# LAN8870_PINOUT.net
KiCad netlist of a schematic drawn in Altium Designer
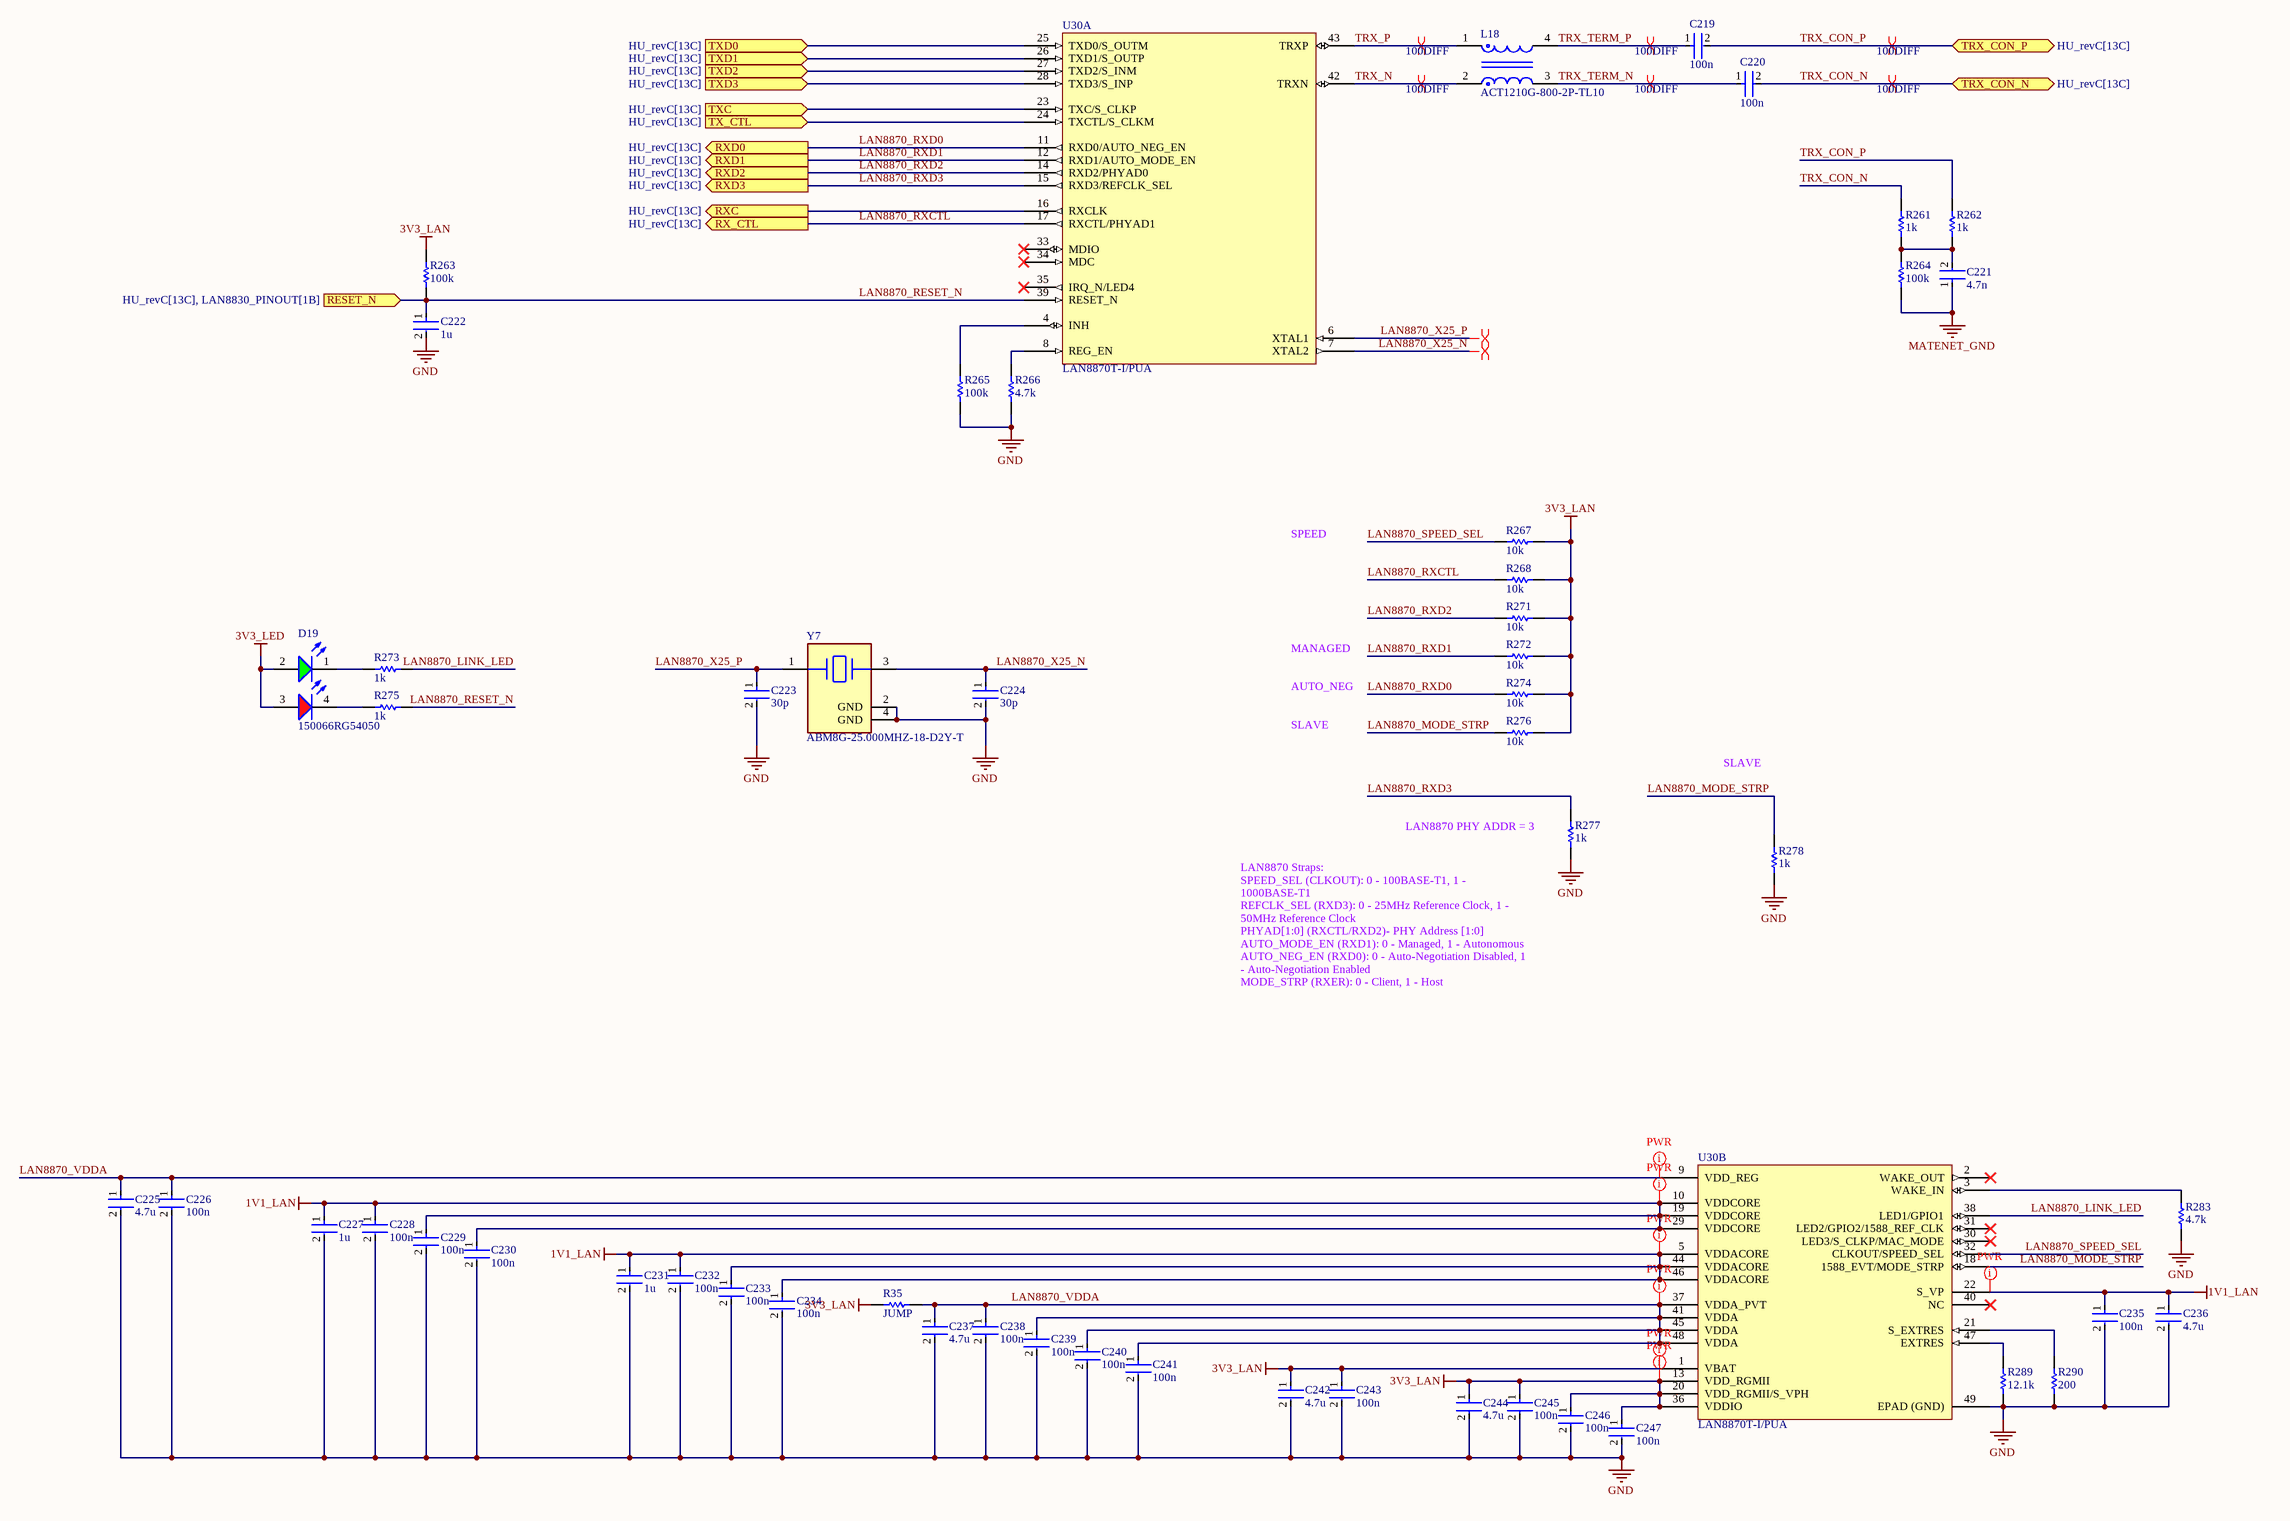
[diagram p0: LAN8870_PINOUT.SchDoc]

(export (version "E")
  (design (tool "Eeschema 10.0.6"))
  (components
    (comp (ref "C219")
      (value "100n")
      (footprint "FP-0402-L_1_0_0_05-W_0_5-IPC_A")
      (description "LARGE PADS, 0402 CAP, CHANGE COMMENT TO MATCH REAL P/N")
      (libsource (lib "Space Concordia") (part "b4654b650e69147ec39a6b967a45e02"))
    )
    (comp (ref "C220")
      (value "100n")
      (footprint "FP-0402-L_1_0_0_05-W_0_5-IPC_A")
      (description "LARGE PADS, 0402 CAP, CHANGE COMMENT TO MATCH REAL P/N")
      (libsource (lib "Space Concordia") (part "b4654b650e69147ec39a6b967a45e02"))
    )
    (comp (ref "C221")
      (value "4.7n")
      (footprint "FP-0402-L_1_0_0_05-W_0_5-IPC_A")
      (description "LARGE PADS, 0402 CAP, CHANGE COMMENT TO MATCH REAL P/N")
      (libsource (lib "Space Concordia") (part "b4654b650e69147ec39a6b967a45e02"))
    )
    (comp (ref "C222")
      (value "1u")
      (footprint "FP-0402-L_1_0_0_05-W_0_5-IPC_A")
      (description "LARGE PADS, 0402 CAP, CHANGE COMMENT TO MATCH REAL P/N")
      (libsource (lib "Space Concordia") (part "b4654b650e69147ec39a6b967a45e02"))
    )
    (comp (ref "C223")
      (value "30p")
      (footprint "FP-0402-L_1_0_0_05-W_0_5-IPC_A")
      (description "LARGE PADS, 0402 CAP, CHANGE COMMENT TO MATCH REAL P/N")
      (libsource (lib "Space Concordia") (part "b4654b650e69147ec39a6b967a45e02"))
    )
    (comp (ref "C224")
      (value "30p")
      (footprint "FP-0402-L_1_0_0_05-W_0_5-IPC_A")
      (description "LARGE PADS, 0402 CAP, CHANGE COMMENT TO MATCH REAL P/N")
      (libsource (lib "Space Concordia") (part "b4654b650e69147ec39a6b967a45e02"))
    )
    (comp (ref "C225")
      (value "4.7u")
      (footprint "FP-0402-L_1_0_0_05-W_0_5-IPC_A")
      (description "LARGE PADS, 0402 CAP, CHANGE COMMENT TO MATCH REAL P/N")
      (libsource (lib "Space Concordia") (part "b4654b650e69147ec39a6b967a45e02"))
    )
    (comp (ref "C226")
      (value "100n")
      (footprint "FP-0402-L_1_0_0_05-W_0_5-IPC_A")
      (description "LARGE PADS, 0402 CAP, CHANGE COMMENT TO MATCH REAL P/N")
      (libsource (lib "Space Concordia") (part "b4654b650e69147ec39a6b967a45e02"))
    )
    (comp (ref "C227")
      (value "1u")
      (footprint "FP-0402-L_1_0_0_05-W_0_5-IPC_A")
      (description "LARGE PADS, 0402 CAP, CHANGE COMMENT TO MATCH REAL P/N")
      (libsource (lib "Space Concordia") (part "b4654b650e69147ec39a6b967a45e02"))
    )
    (comp (ref "C228")
      (value "100n")
      (footprint "FP-0402-L_1_0_0_05-W_0_5-IPC_A")
      (description "LARGE PADS, 0402 CAP, CHANGE COMMENT TO MATCH REAL P/N")
      (libsource (lib "Space Concordia") (part "b4654b650e69147ec39a6b967a45e02"))
    )
    (comp (ref "C229")
      (value "100n")
      (footprint "FP-0402-L_1_0_0_05-W_0_5-IPC_A")
      (description "LARGE PADS, 0402 CAP, CHANGE COMMENT TO MATCH REAL P/N")
      (libsource (lib "Space Concordia") (part "b4654b650e69147ec39a6b967a45e02"))
    )
    (comp (ref "C230")
      (value "100n")
      (footprint "FP-0402-L_1_0_0_05-W_0_5-IPC_A")
      (description "LARGE PADS, 0402 CAP, CHANGE COMMENT TO MATCH REAL P/N")
      (libsource (lib "Space Concordia") (part "b4654b650e69147ec39a6b967a45e02"))
    )
    (comp (ref "C231")
      (value "1u")
      (footprint "FP-0402-L_1_0_0_05-W_0_5-IPC_A")
      (description "LARGE PADS, 0402 CAP, CHANGE COMMENT TO MATCH REAL P/N")
      (libsource (lib "Space Concordia") (part "b4654b650e69147ec39a6b967a45e02"))
    )
    (comp (ref "C232")
      (value "100n")
      (footprint "FP-0402-L_1_0_0_05-W_0_5-IPC_A")
      (description "LARGE PADS, 0402 CAP, CHANGE COMMENT TO MATCH REAL P/N")
      (libsource (lib "Space Concordia") (part "b4654b650e69147ec39a6b967a45e02"))
    )
    (comp (ref "C233")
      (value "100n")
      (footprint "FP-0402-L_1_0_0_05-W_0_5-IPC_A")
      (description "LARGE PADS, 0402 CAP, CHANGE COMMENT TO MATCH REAL P/N")
      (libsource (lib "Space Concordia") (part "b4654b650e69147ec39a6b967a45e02"))
    )
    (comp (ref "C234")
      (value "100n")
      (footprint "FP-0402-L_1_0_0_05-W_0_5-IPC_A")
      (description "LARGE PADS, 0402 CAP, CHANGE COMMENT TO MATCH REAL P/N")
      (libsource (lib "Space Concordia") (part "b4654b650e69147ec39a6b967a45e02"))
    )
    (comp (ref "C235")
      (value "100n")
      (footprint "FP-0402-L_1_0_0_05-W_0_5-IPC_A")
      (description "LARGE PADS, 0402 CAP, CHANGE COMMENT TO MATCH REAL P/N")
      (libsource (lib "Space Concordia") (part "b4654b650e69147ec39a6b967a45e02"))
    )
    (comp (ref "C236")
      (value "4.7u")
      (footprint "FP-0402-L_1_0_0_05-W_0_5-IPC_A")
      (description "LARGE PADS, 0402 CAP, CHANGE COMMENT TO MATCH REAL P/N")
      (libsource (lib "Space Concordia") (part "b4654b650e69147ec39a6b967a45e02"))
    )
    (comp (ref "C237")
      (value "4.7u")
      (footprint "FP-0402-L_1_0_0_05-W_0_5-IPC_A")
      (description "LARGE PADS, 0402 CAP, CHANGE COMMENT TO MATCH REAL P/N")
      (libsource (lib "Space Concordia") (part "b4654b650e69147ec39a6b967a45e02"))
    )
    (comp (ref "C238")
      (value "100n")
      (footprint "FP-0402-L_1_0_0_05-W_0_5-IPC_A")
      (description "LARGE PADS, 0402 CAP, CHANGE COMMENT TO MATCH REAL P/N")
      (libsource (lib "Space Concordia") (part "b4654b650e69147ec39a6b967a45e02"))
    )
    (comp (ref "C239")
      (value "100n")
      (footprint "FP-0402-L_1_0_0_05-W_0_5-IPC_A")
      (description "LARGE PADS, 0402 CAP, CHANGE COMMENT TO MATCH REAL P/N")
      (libsource (lib "Space Concordia") (part "b4654b650e69147ec39a6b967a45e02"))
    )
    (comp (ref "C240")
      (value "100n")
      (footprint "FP-0402-L_1_0_0_05-W_0_5-IPC_A")
      (description "LARGE PADS, 0402 CAP, CHANGE COMMENT TO MATCH REAL P/N")
      (libsource (lib "Space Concordia") (part "b4654b650e69147ec39a6b967a45e02"))
    )
    (comp (ref "C241")
      (value "100n")
      (footprint "FP-0402-L_1_0_0_05-W_0_5-IPC_A")
      (description "LARGE PADS, 0402 CAP, CHANGE COMMENT TO MATCH REAL P/N")
      (libsource (lib "Space Concordia") (part "b4654b650e69147ec39a6b967a45e02"))
    )
    (comp (ref "C242")
      (value "4.7u")
      (footprint "FP-0402-L_1_0_0_05-W_0_5-IPC_A")
      (description "LARGE PADS, 0402 CAP, CHANGE COMMENT TO MATCH REAL P/N")
      (libsource (lib "Space Concordia") (part "b4654b650e69147ec39a6b967a45e02"))
    )
    (comp (ref "C243")
      (value "100n")
      (footprint "FP-0402-L_1_0_0_05-W_0_5-IPC_A")
      (description "LARGE PADS, 0402 CAP, CHANGE COMMENT TO MATCH REAL P/N")
      (libsource (lib "Space Concordia") (part "b4654b650e69147ec39a6b967a45e02"))
    )
    (comp (ref "C244")
      (value "4.7u")
      (footprint "FP-0402-L_1_0_0_05-W_0_5-IPC_A")
      (description "LARGE PADS, 0402 CAP, CHANGE COMMENT TO MATCH REAL P/N")
      (libsource (lib "Space Concordia") (part "b4654b650e69147ec39a6b967a45e02"))
    )
    (comp (ref "C245")
      (value "100n")
      (footprint "FP-0402-L_1_0_0_05-W_0_5-IPC_A")
      (description "LARGE PADS, 0402 CAP, CHANGE COMMENT TO MATCH REAL P/N")
      (libsource (lib "Space Concordia") (part "b4654b650e69147ec39a6b967a45e02"))
    )
    (comp (ref "C246")
      (value "100n")
      (footprint "FP-0402-L_1_0_0_05-W_0_5-IPC_A")
      (description "LARGE PADS, 0402 CAP, CHANGE COMMENT TO MATCH REAL P/N")
      (libsource (lib "Space Concordia") (part "b4654b650e69147ec39a6b967a45e02"))
    )
    (comp (ref "C247")
      (value "100n")
      (footprint "FP-0402-L_1_0_0_05-W_0_5-IPC_A")
      (description "LARGE PADS, 0402 CAP, CHANGE COMMENT TO MATCH REAL P/N")
      (libsource (lib "Space Concordia") (part "b4654b650e69147ec39a6b967a45e02"))
    )
    (comp (ref "D19")
      (value "150066RG54050")
      (footprint "WL-SBCD_0606")
      (description "Led, Red/Grn, 180Mcd/230Mcd, 624Nm/525Nm Rohs Compliant: Yes")
      (fields (field (name "SOURCE") "rgled.SchLib"))
      (libsource (lib "Space Concordia") (part "CMP-004-00034-2"))
    )
    (comp (ref "L18")
      (value "ACT1210G-800-2P-TL10")
      (footprint "FP-ACT1210G-800-2P-TL10-MFG")
      (description "CMC 80UH 70MA 2LN 3.8KOHM SMD")
      (libsource (lib "Altium Content Vault") (part "b4b74a627ea9af473eaab86227aab92"))
    )
    (comp (ref "R35")
      (value "JUMP")
      (footprint "R0603B")
      (description "Resistor")
      (libsource (lib "Space Concordia") (part "Resistor"))
    )
    (comp (ref "R261")
      (value "1k")
      (footprint "R0603B")
      (description "Resistor")
      (libsource (lib "Space Concordia") (part "Resistor"))
    )
    (comp (ref "R262")
      (value "1k")
      (footprint "R0603B")
      (description "Resistor")
      (libsource (lib "Space Concordia") (part "Resistor"))
    )
    (comp (ref "R263")
      (value "100k")
      (footprint "R0603B")
      (description "Resistor")
      (libsource (lib "Space Concordia") (part "Resistor"))
    )
    (comp (ref "R264")
      (value "100k")
      (footprint "R0603B")
      (description "Resistor")
      (libsource (lib "Space Concordia") (part "Resistor"))
    )
    (comp (ref "R265")
      (value "100k")
      (footprint "R0603B")
      (description "Resistor")
      (libsource (lib "Space Concordia") (part "Resistor"))
    )
    (comp (ref "R266")
      (value "4.7k")
      (footprint "R0603B")
      (description "Resistor")
      (libsource (lib "Space Concordia") (part "Resistor"))
    )
    (comp (ref "R267")
      (value "10k")
      (footprint "R0603B")
      (description "Resistor")
      (libsource (lib "Space Concordia") (part "Resistor"))
    )
    (comp (ref "R268")
      (value "10k")
      (footprint "R0603B")
      (description "Resistor")
      (libsource (lib "Space Concordia") (part "Resistor"))
    )
    (comp (ref "R271")
      (value "10k")
      (footprint "R0603B")
      (description "Resistor")
      (libsource (lib "Space Concordia") (part "Resistor"))
    )
    (comp (ref "R272")
      (value "10k")
      (footprint "R0603B")
      (description "Resistor")
      (libsource (lib "Space Concordia") (part "Resistor"))
    )
    (comp (ref "R273")
      (value "1k")
      (footprint "R0603B")
      (description "Resistor")
      (libsource (lib "Space Concordia") (part "Resistor"))
    )
    (comp (ref "R274")
      (value "10k")
      (footprint "R0603B")
      (description "Resistor")
      (libsource (lib "Space Concordia") (part "Resistor"))
    )
    (comp (ref "R275")
      (value "1k")
      (footprint "R0603B")
      (description "Resistor")
      (libsource (lib "Space Concordia") (part "Resistor"))
    )
    (comp (ref "R276")
      (value "10k")
      (footprint "R0603B")
      (description "Resistor")
      (libsource (lib "Space Concordia") (part "Resistor"))
    )
    (comp (ref "R277")
      (value "1k")
      (footprint "R0603B")
      (description "Resistor")
      (libsource (lib "Space Concordia") (part "Resistor"))
    )
    (comp (ref "R278")
      (value "1k")
      (footprint "R0603B")
      (description "Resistor")
      (libsource (lib "Space Concordia") (part "Resistor"))
    )
    (comp (ref "R283")
      (value "4.7k")
      (footprint "R0603B")
      (description "Resistor")
      (libsource (lib "Space Concordia") (part "Resistor"))
    )
    (comp (ref "R289")
      (value "12.1k")
      (footprint "R0603B")
      (description "Resistor")
      (libsource (lib "Space Concordia") (part "Resistor"))
    )
    (comp (ref "R290")
      (value "200")
      (footprint "R0603B")
      (description "Resistor")
      (libsource (lib "Space Concordia") (part "Resistor"))
    )
    (comp (ref "U30")
      (value "LAN8870T-I/PUA")
      (footprint "QFN50P700X700X100_HS-49N")
      (description "100/1000BASE-T1 Rgmii/sgmii Phy")
      (libsource (lib "Space Concordia") (part "LAN8870T-I_PUA"))
    )
    (comp (ref "Y7")
      (value "ABM8G-25.000MHZ-18-D2Y-T")
      (footprint "FP-ABM8G-MFG")
      (description "Crystal 25MHz ±20ppm (Tol) ±30ppm (Stability) 18pF FUND 60Ω 4-Pin SMD T/R")
      (fields (field (name "TOLERANCE") "20ppm"))
      (libsource (lib "Altium Content Vault") (part "48e526d86b7f2615d98721063c72f49"))
    )
  )
  (nets
    (net (code "1") (name "/LAN8870_LINK_LED") (class "Default")
      (node (ref "R273") (pin "2") (pinfunction "2_2") (pintype "passive"))
      (node (ref "U30") (pin "38") (pinfunction "LED1/GPIO1_38") (pintype "bidirectional"))
    )
    (net (code "2") (name "/LAN8870_MODE_STRP") (class "Default")
      (node (ref "R276") (pin "1") (pinfunction "1_1") (pintype "passive"))
      (node (ref "R278") (pin "2") (pinfunction "2_2") (pintype "passive"))
      (node (ref "U30") (pin "18") (pinfunction "1588_EVT/MODE_STRP_18") (pintype "bidirectional"))
    )
    (net (code "3") (name "/LAN8870_RESET_N") (class "Default")
      (node (ref "C222") (pin "1") (pinfunction "1_1") (pintype "passive"))
      (node (ref "R263") (pin "2") (pinfunction "2_2") (pintype "passive"))
      (node (ref "R275") (pin "2") (pinfunction "2_2") (pintype "passive"))
      (node (ref "U30") (pin "39") (pinfunction "RESET_N_39") (pintype "input"))
    )
    (net (code "4") (name "/LAN8870_RXCTL") (class "Default")
      (node (ref "R268") (pin "2") (pinfunction "2_2") (pintype "passive"))
      (node (ref "U30") (pin "17") (pinfunction "RXCTL/PHYAD1_17") (pintype "output"))
    )
    (net (code "5") (name "/LAN8870_RXD0") (class "Default")
      (node (ref "R274") (pin "1") (pinfunction "1_1") (pintype "passive"))
      (node (ref "U30") (pin "11") (pinfunction "RXD0/AUTO_NEG_EN_11") (pintype "output"))
    )
    (net (code "6") (name "/LAN8870_RXD1") (class "Default")
      (node (ref "R272") (pin "1") (pinfunction "1_1") (pintype "passive"))
      (node (ref "U30") (pin "12") (pinfunction "RXD1/AUTO_MODE_EN_12") (pintype "output"))
    )
    (net (code "7") (name "/LAN8870_RXD2") (class "Default")
      (node (ref "R271") (pin "1") (pinfunction "1_1") (pintype "passive"))
      (node (ref "U30") (pin "14") (pinfunction "RXD2/PHYAD0_14") (pintype "output"))
    )
    (net (code "8") (name "/LAN8870_RXD3") (class "Default")
      (node (ref "R277") (pin "2") (pinfunction "2_2") (pintype "passive"))
      (node (ref "U30") (pin "15") (pinfunction "RXD3/REFCLK_SEL_15") (pintype "output"))
    )
    (net (code "9") (name "/LAN8870_SPEED_SEL") (class "Default")
      (node (ref "R267") (pin "1") (pinfunction "1_1") (pintype "passive"))
      (node (ref "U30") (pin "32") (pinfunction "CLKOUT/SPEED_SEL_32") (pintype "bidirectional"))
    )
    (net (code "10") (name "/LAN8870_VDDA") (class "Default")
      (node (ref "C225") (pin "1") (pinfunction "1_1") (pintype "passive"))
      (node (ref "C226") (pin "1") (pinfunction "1_1") (pintype "passive"))
      (node (ref "C237") (pin "1") (pinfunction "1_1") (pintype "passive"))
      (node (ref "C238") (pin "1") (pinfunction "1_1") (pintype "passive"))
      (node (ref "C239") (pin "1") (pinfunction "1_1") (pintype "passive"))
      (node (ref "C240") (pin "1") (pinfunction "1_1") (pintype "passive"))
      (node (ref "C241") (pin "1") (pinfunction "1_1") (pintype "passive"))
      (node (ref "R35") (pin "2") (pinfunction "2_2") (pintype "passive"))
      (node (ref "U30") (pin "37") (pinfunction "VDDA_PVT_37") (pintype "power_in"))
      (node (ref "U30") (pin "41") (pinfunction "VDDA_41") (pintype "power_in"))
      (node (ref "U30") (pin "45") (pinfunction "VDDA_45") (pintype "power_in"))
      (node (ref "U30") (pin "48") (pinfunction "VDDA_48") (pintype "power_in"))
      (node (ref "U30") (pin "9") (pinfunction "VDD_REG_9") (pintype "power_in"))
    )
    (net (code "11") (name "/LAN8870_X25_N") (class "Default")
      (node (ref "C224") (pin "1") (pinfunction "1_1") (pintype "passive"))
      (node (ref "U30") (pin "7") (pinfunction "XTAL2_7") (pintype "output"))
      (node (ref "Y7") (pin "3") (pinfunction "3_3") (pintype "passive"))
    )
    (net (code "12") (name "/LAN8870_X25_P") (class "Default")
      (node (ref "C223") (pin "1") (pinfunction "1_1") (pintype "passive"))
      (node (ref "U30") (pin "6") (pinfunction "XTAL1_6") (pintype "input"))
      (node (ref "Y7") (pin "1") (pinfunction "1_1") (pintype "passive"))
    )
    (net (code "13") (name "/RXC") (class "Default")
      (node (ref "U30") (pin "16") (pinfunction "RXCLK_16") (pintype "output"))
    )
    (net (code "14") (name "/TRX_CON_N") (class "Default")
      (node (ref "C220") (pin "2") (pinfunction "2_2") (pintype "passive"))
      (node (ref "R261") (pin "2") (pinfunction "2_2") (pintype "passive"))
    )
    (net (code "15") (name "/TRX_CON_P") (class "Default")
      (node (ref "C219") (pin "2") (pinfunction "2_2") (pintype "passive"))
      (node (ref "R262") (pin "2") (pinfunction "2_2") (pintype "passive"))
    )
    (net (code "16") (name "/TRX_N") (class "Default")
      (node (ref "L18") (pin "2") (pinfunction "2_2") (pintype "passive"))
      (node (ref "U30") (pin "42") (pinfunction "TRXN_42") (pintype "bidirectional"))
    )
    (net (code "17") (name "/TRX_P") (class "Default")
      (node (ref "L18") (pin "1") (pinfunction "1_1") (pintype "passive"))
      (node (ref "U30") (pin "43") (pinfunction "TRXP_43") (pintype "bidirectional"))
    )
    (net (code "18") (name "/TRX_TERM_N") (class "Default")
      (node (ref "C220") (pin "1") (pinfunction "1_1") (pintype "passive"))
      (node (ref "L18") (pin "3") (pinfunction "3_3") (pintype "passive"))
    )
    (net (code "19") (name "/TRX_TERM_P") (class "Default")
      (node (ref "C219") (pin "1") (pinfunction "1_1") (pintype "passive"))
      (node (ref "L18") (pin "4") (pinfunction "4_4") (pintype "passive"))
    )
    (net (code "20") (name "/TXC") (class "Default")
      (node (ref "U30") (pin "23") (pinfunction "TXC/S_CLKP_23") (pintype "input"))
    )
    (net (code "21") (name "/TXD0") (class "Default")
      (node (ref "U30") (pin "25") (pinfunction "TXD0/S_OUTM_25") (pintype "input"))
    )
    (net (code "22") (name "/TXD1") (class "Default")
      (node (ref "U30") (pin "26") (pinfunction "TXD1/S_OUTP_26") (pintype "input"))
    )
    (net (code "23") (name "/TXD2") (class "Default")
      (node (ref "U30") (pin "27") (pinfunction "TXD2/S_INM_27") (pintype "input"))
    )
    (net (code "24") (name "/TXD3") (class "Default")
      (node (ref "U30") (pin "28") (pinfunction "TXD3/S_INP_28") (pintype "input"))
    )
    (net (code "25") (name "/TX_CTL") (class "Default")
      (node (ref "U30") (pin "24") (pinfunction "TXCTL/S_CLKM_24") (pintype "input"))
    )
    (net (code "26") (name "1V1_LAN") (class "Default")
      (node (ref "C227") (pin "1") (pinfunction "1_1") (pintype "passive"))
      (node (ref "C228") (pin "1") (pinfunction "1_1") (pintype "passive"))
      (node (ref "C229") (pin "1") (pinfunction "1_1") (pintype "passive"))
      (node (ref "C230") (pin "1") (pinfunction "1_1") (pintype "passive"))
      (node (ref "C231") (pin "1") (pinfunction "1_1") (pintype "passive"))
      (node (ref "C232") (pin "1") (pinfunction "1_1") (pintype "passive"))
      (node (ref "C233") (pin "1") (pinfunction "1_1") (pintype "passive"))
      (node (ref "C234") (pin "1") (pinfunction "1_1") (pintype "passive"))
      (node (ref "C235") (pin "1") (pinfunction "1_1") (pintype "passive"))
      (node (ref "C236") (pin "1") (pinfunction "1_1") (pintype "passive"))
      (node (ref "U30") (pin "10") (pinfunction "VDDCORE_10") (pintype "power_in"))
      (node (ref "U30") (pin "19") (pinfunction "VDDCORE_19") (pintype "power_in"))
      (node (ref "U30") (pin "22") (pinfunction "S_VP_22") (pintype "passive"))
      (node (ref "U30") (pin "29") (pinfunction "VDDCORE_29") (pintype "power_in"))
      (node (ref "U30") (pin "44") (pinfunction "VDDACORE_44") (pintype "power_in"))
      (node (ref "U30") (pin "46") (pinfunction "VDDACORE_46") (pintype "power_in"))
      (node (ref "U30") (pin "5") (pinfunction "VDDACORE_5") (pintype "power_in"))
    )
    (net (code "27") (name "3V3_LAN") (class "Default")
      (node (ref "C242") (pin "1") (pinfunction "1_1") (pintype "passive"))
      (node (ref "C243") (pin "1") (pinfunction "1_1") (pintype "passive"))
      (node (ref "C244") (pin "1") (pinfunction "1_1") (pintype "passive"))
      (node (ref "C245") (pin "1") (pinfunction "1_1") (pintype "passive"))
      (node (ref "C246") (pin "1") (pinfunction "1_1") (pintype "passive"))
      (node (ref "C247") (pin "1") (pinfunction "1_1") (pintype "passive"))
      (node (ref "R263") (pin "1") (pinfunction "1_1") (pintype "passive"))
      (node (ref "R267") (pin "2") (pinfunction "2_2") (pintype "passive"))
      (node (ref "R268") (pin "1") (pinfunction "1_1") (pintype "passive"))
      (node (ref "R271") (pin "2") (pinfunction "2_2") (pintype "passive"))
      (node (ref "R272") (pin "2") (pinfunction "2_2") (pintype "passive"))
      (node (ref "R274") (pin "2") (pinfunction "2_2") (pintype "passive"))
      (node (ref "R276") (pin "2") (pinfunction "2_2") (pintype "passive"))
      (node (ref "R35") (pin "1") (pinfunction "1_1") (pintype "passive"))
      (node (ref "U30") (pin "1") (pinfunction "VBAT_1") (pintype "power_in"))
      (node (ref "U30") (pin "13") (pinfunction "VDD_RGMII_13") (pintype "power_in"))
      (node (ref "U30") (pin "20") (pinfunction "VDD_RGMII/S_VPH_20") (pintype "power_in"))
      (node (ref "U30") (pin "36") (pinfunction "VDDIO_36") (pintype "power_in"))
    )
    (net (code "28") (name "3V3_LED") (class "Default")
      (node (ref "D19") (pin "2") (pinfunction "A_2") (pintype "passive"))
      (node (ref "D19") (pin "3") (pinfunction "A_3") (pintype "passive"))
    )
    (net (code "29") (name "GND") (class "Default")
      (node (ref "C222") (pin "2") (pinfunction "2_2") (pintype "passive"))
      (node (ref "C223") (pin "2") (pinfunction "2_2") (pintype "passive"))
      (node (ref "C224") (pin "2") (pinfunction "2_2") (pintype "passive"))
      (node (ref "C225") (pin "2") (pinfunction "2_2") (pintype "passive"))
      (node (ref "C226") (pin "2") (pinfunction "2_2") (pintype "passive"))
      (node (ref "C227") (pin "2") (pinfunction "2_2") (pintype "passive"))
      (node (ref "C228") (pin "2") (pinfunction "2_2") (pintype "passive"))
      (node (ref "C229") (pin "2") (pinfunction "2_2") (pintype "passive"))
      (node (ref "C230") (pin "2") (pinfunction "2_2") (pintype "passive"))
      (node (ref "C231") (pin "2") (pinfunction "2_2") (pintype "passive"))
      (node (ref "C232") (pin "2") (pinfunction "2_2") (pintype "passive"))
      (node (ref "C233") (pin "2") (pinfunction "2_2") (pintype "passive"))
      (node (ref "C234") (pin "2") (pinfunction "2_2") (pintype "passive"))
      (node (ref "C235") (pin "2") (pinfunction "2_2") (pintype "passive"))
      (node (ref "C236") (pin "2") (pinfunction "2_2") (pintype "passive"))
      (node (ref "C237") (pin "2") (pinfunction "2_2") (pintype "passive"))
      (node (ref "C238") (pin "2") (pinfunction "2_2") (pintype "passive"))
      (node (ref "C239") (pin "2") (pinfunction "2_2") (pintype "passive"))
      (node (ref "C240") (pin "2") (pinfunction "2_2") (pintype "passive"))
      (node (ref "C241") (pin "2") (pinfunction "2_2") (pintype "passive"))
      (node (ref "C242") (pin "2") (pinfunction "2_2") (pintype "passive"))
      (node (ref "C243") (pin "2") (pinfunction "2_2") (pintype "passive"))
      (node (ref "C244") (pin "2") (pinfunction "2_2") (pintype "passive"))
      (node (ref "C245") (pin "2") (pinfunction "2_2") (pintype "passive"))
      (node (ref "C246") (pin "2") (pinfunction "2_2") (pintype "passive"))
      (node (ref "C247") (pin "2") (pinfunction "2_2") (pintype "passive"))
      (node (ref "R265") (pin "2") (pinfunction "2_2") (pintype "passive"))
      (node (ref "R266") (pin "2") (pinfunction "2_2") (pintype "passive"))
      (node (ref "R277") (pin "1") (pinfunction "1_1") (pintype "passive"))
      (node (ref "R278") (pin "1") (pinfunction "1_1") (pintype "passive"))
      (node (ref "R283") (pin "2") (pinfunction "2_2") (pintype "passive"))
      (node (ref "R289") (pin "2") (pinfunction "2_2") (pintype "passive"))
      (node (ref "R290") (pin "2") (pinfunction "2_2") (pintype "passive"))
      (node (ref "U30") (pin "49") (pinfunction "EPAD_(GND)_49") (pintype "power_in"))
      (node (ref "Y7") (pin "2") (pinfunction "GND_2") (pintype "power_in"))
      (node (ref "Y7") (pin "4") (pinfunction "GND_4") (pintype "power_in"))
    )
    (net (code "30") (name "MATENET_GND") (class "Default")
      (node (ref "C221") (pin "1") (pinfunction "1_1") (pintype "passive"))
      (node (ref "R264") (pin "2") (pinfunction "2_2") (pintype "passive"))
    )
    (net (code "31") (name "Net-(C221-Pad2)") (class "Default")
      (node (ref "C221") (pin "2") (pinfunction "2_2") (pintype "passive"))
      (node (ref "R261") (pin "1") (pinfunction "1_1") (pintype "passive"))
      (node (ref "R262") (pin "1") (pinfunction "1_1") (pintype "passive"))
      (node (ref "R264") (pin "1") (pinfunction "1_1") (pintype "passive"))
    )
    (net (code "32") (name "Net-(D19-K-Pad1)") (class "Default")
      (node (ref "D19") (pin "1") (pinfunction "K_1") (pintype "passive"))
      (node (ref "R273") (pin "1") (pinfunction "1_1") (pintype "passive"))
    )
    (net (code "33") (name "Net-(D19-K-Pad4)") (class "Default")
      (node (ref "D19") (pin "4") (pinfunction "K_4") (pintype "passive"))
      (node (ref "R275") (pin "1") (pinfunction "1_1") (pintype "passive"))
    )
    (net (code "34") (name "Net-(U30A-INH)") (class "Default")
      (node (ref "R265") (pin "1") (pinfunction "1_1") (pintype "passive"))
      (node (ref "U30") (pin "4") (pinfunction "INH_4") (pintype "bidirectional"))
    )
    (net (code "35") (name "Net-(U30A-REG_EN)") (class "Default")
      (node (ref "R266") (pin "1") (pinfunction "1_1") (pintype "passive"))
      (node (ref "U30") (pin "8") (pinfunction "REG_EN_8") (pintype "input"))
    )
    (net (code "36") (name "Net-(U30B-EXTRES)") (class "Default")
      (node (ref "R289") (pin "1") (pinfunction "1_1") (pintype "passive"))
      (node (ref "U30") (pin "47") (pinfunction "EXTRES_47") (pintype "input"))
    )
    (net (code "37") (name "Net-(U30B-S_EXTRES)") (class "Default")
      (node (ref "R290") (pin "1") (pinfunction "1_1") (pintype "passive"))
      (node (ref "U30") (pin "21") (pinfunction "S_EXTRES_21") (pintype "input"))
    )
    (net (code "38") (name "Net-(U30B-WAKE_IN)") (class "Default")
      (node (ref "R283") (pin "1") (pinfunction "1_1") (pintype "passive"))
      (node (ref "U30") (pin "3") (pinfunction "WAKE_IN_3") (pintype "bidirectional"))
    )
    (net (code "39") (name "unconnected-(U30A-IRQ_N{slash}LED4-Pad35)") (class "Default")
      (node (ref "U30") (pin "35") (pinfunction "IRQ_N/LED4_35") (pintype "output+no_connect"))
    )
    (net (code "40") (name "unconnected-(U30A-MDC-Pad34)") (class "Default")
      (node (ref "U30") (pin "34") (pinfunction "MDC_34") (pintype "input+no_connect"))
    )
    (net (code "41") (name "unconnected-(U30A-MDIO-Pad33)") (class "Default")
      (node (ref "U30") (pin "33") (pinfunction "MDIO_33") (pintype "bidirectional+no_connect"))
    )
    (net (code "42") (name "unconnected-(U30B-LED2{slash}GPIO2{slash}1588_REF_CLK-Pad31)") (class "Default")
      (node (ref "U30") (pin "31") (pinfunction "LED2/GPIO2/1588_REF_CLK_31") (pintype "bidirectional+no_connect"))
    )
    (net (code "43") (name "unconnected-(U30B-LED3{slash}S_CLKP{slash}MAC_MODE-Pad30)") (class "Default")
      (node (ref "U30") (pin "30") (pinfunction "LED3/S_CLKP/MAC_MODE_30") (pintype "bidirectional+no_connect"))
    )
    (net (code "44") (name "unconnected-(U30B-NC-Pad40)") (class "Default")
      (node (ref "U30") (pin "40") (pinfunction "NC_40") (pintype "passive+no_connect"))
    )
    (net (code "45") (name "unconnected-(U30B-WAKE_OUT-Pad2)") (class "Default")
      (node (ref "U30") (pin "2") (pinfunction "WAKE_OUT_2") (pintype "output+no_connect"))
    )
  )
)
